# digitalBoardV1_1.net
KiCad netlist of a schematic drawn in EAGLE
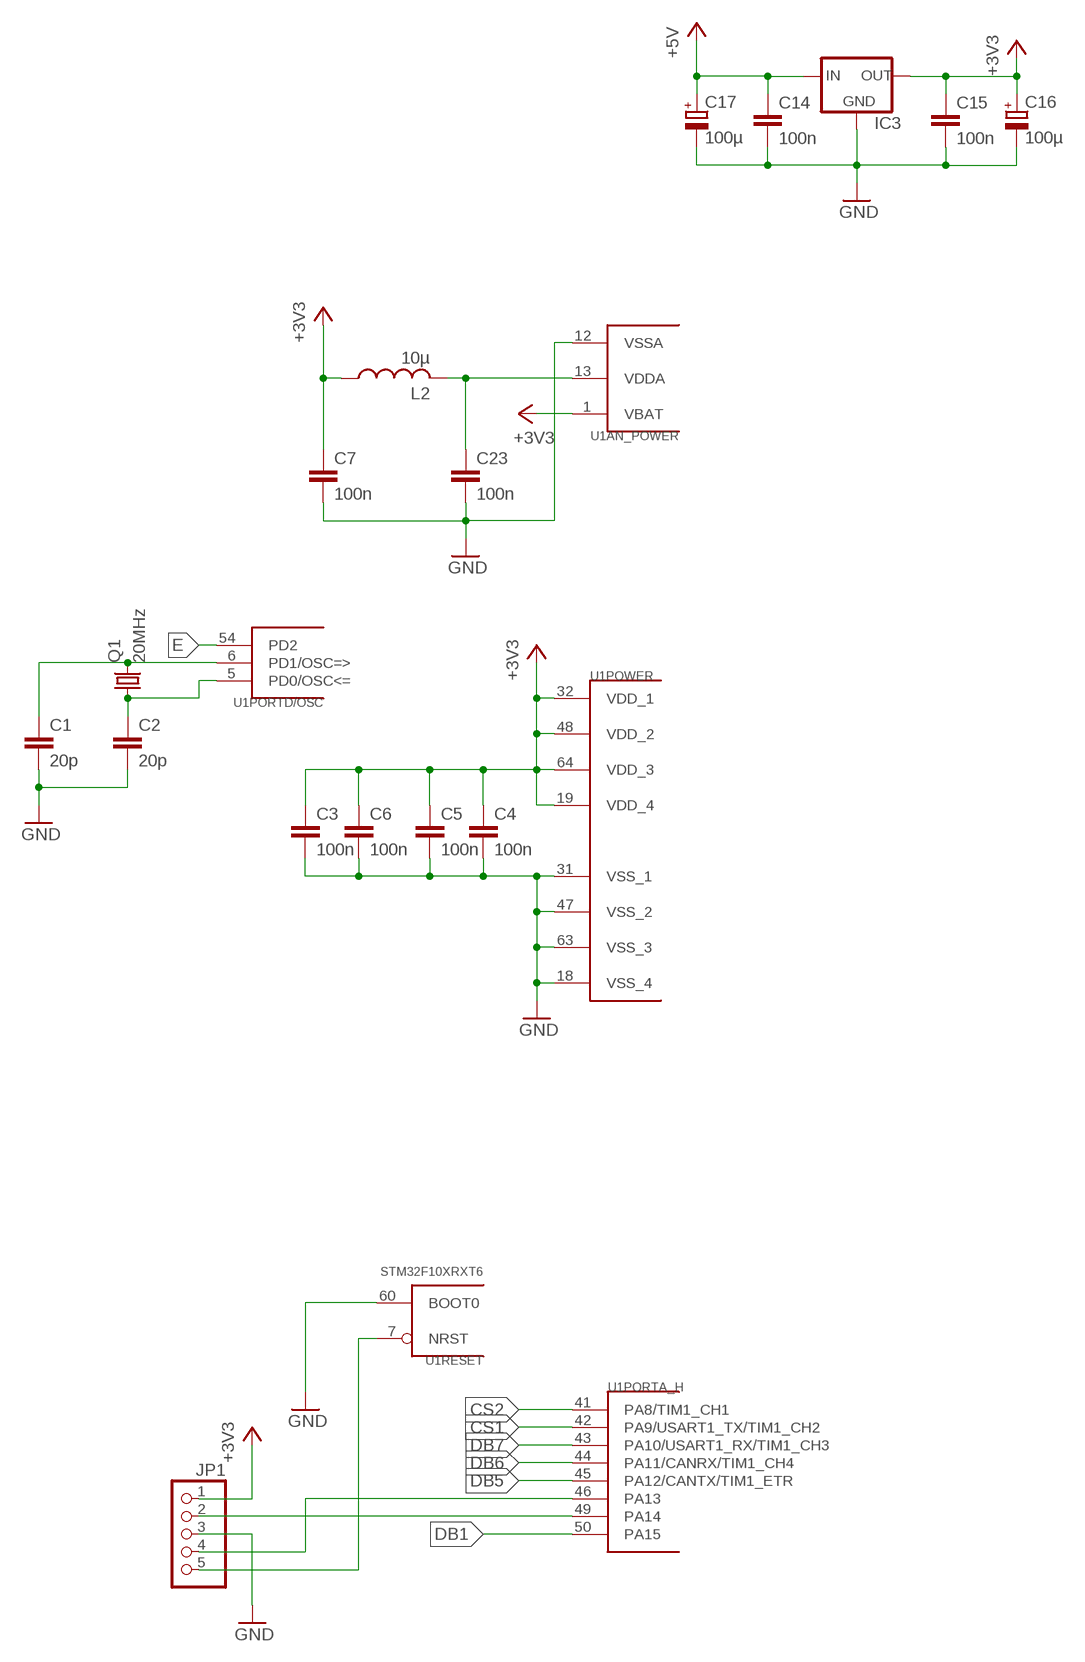
[diagram p0: schematic, sheet 1, part 1 of 2]
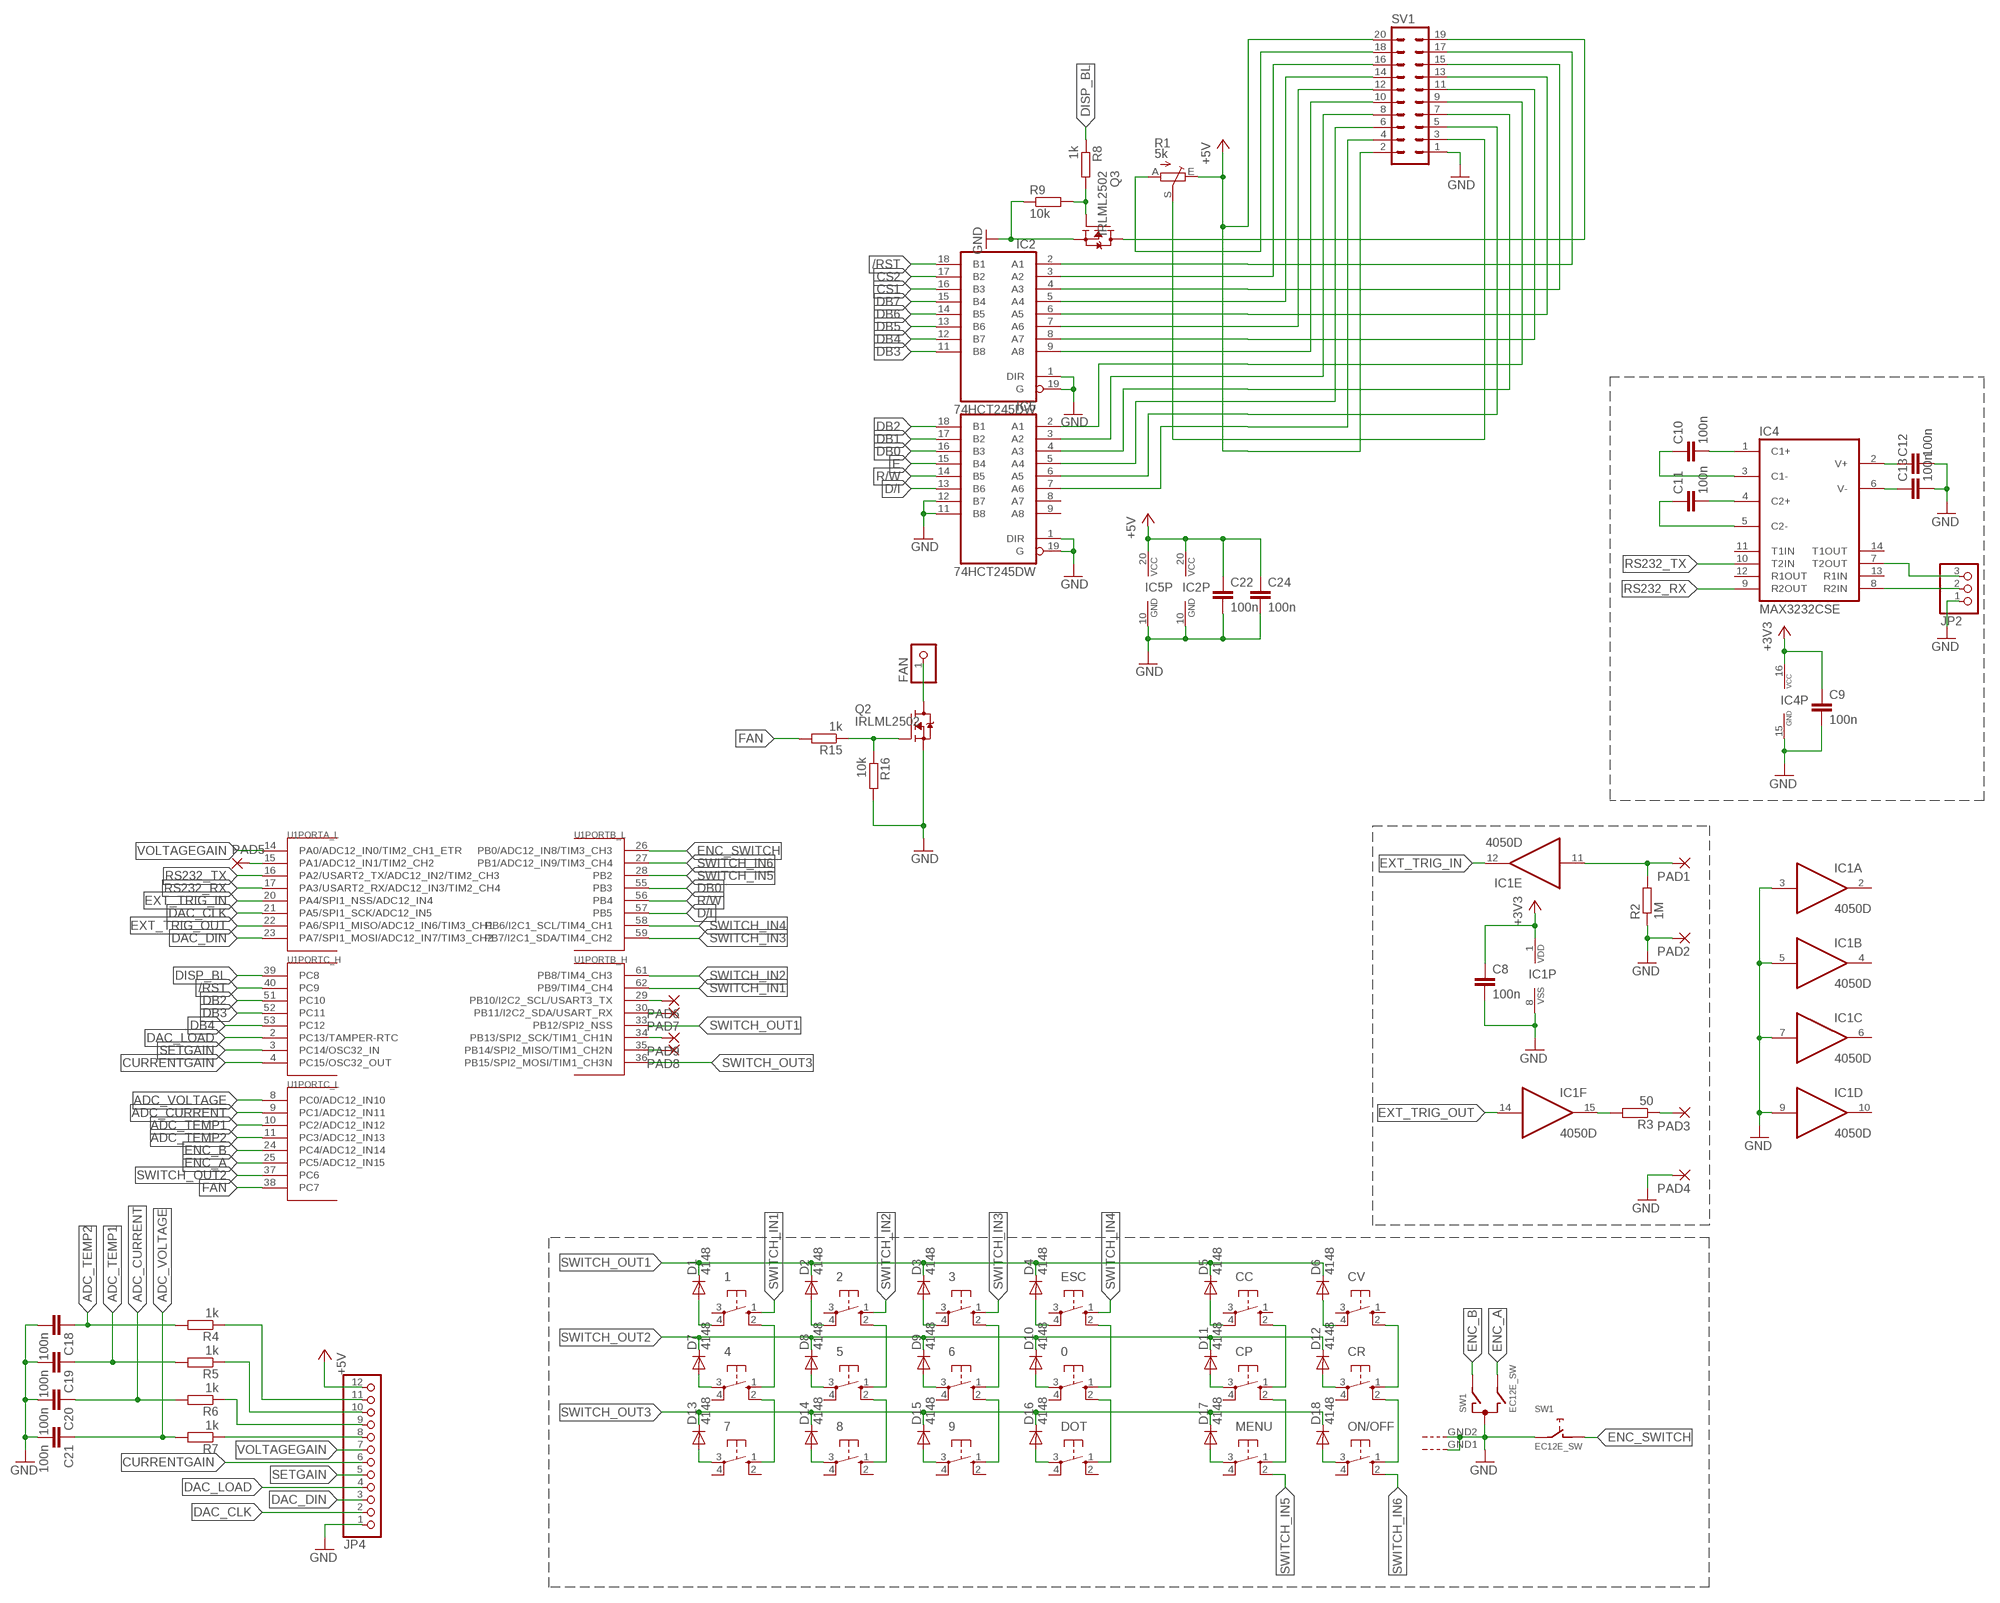
[diagram p1: schematic, sheet 1, part 2 of 2]

(export (version "E")
  (design (tool "Eeschema 10.0.6"))
  (components
    (comp (ref "0")
      (value "10-XXSMD")
      (footprint "eagle-import:SMD")
      (libsource (lib "eagle-import") (part "10-XXSMD"))
    )
    (comp (ref "1")
      (value "10-XXSMD")
      (footprint "eagle-import:SMD")
      (libsource (lib "eagle-import") (part "10-XXSMD"))
    )
    (comp (ref "2")
      (value "10-XXSMD")
      (footprint "eagle-import:SMD")
      (libsource (lib "eagle-import") (part "10-XXSMD"))
    )
    (comp (ref "3")
      (value "10-XXSMD")
      (footprint "eagle-import:SMD")
      (libsource (lib "eagle-import") (part "10-XXSMD"))
    )
    (comp (ref "4")
      (value "10-XXSMD")
      (footprint "eagle-import:SMD")
      (libsource (lib "eagle-import") (part "10-XXSMD"))
    )
    (comp (ref "5")
      (value "10-XXSMD")
      (footprint "eagle-import:SMD")
      (libsource (lib "eagle-import") (part "10-XXSMD"))
    )
    (comp (ref "6")
      (value "10-XXSMD")
      (footprint "eagle-import:SMD")
      (libsource (lib "eagle-import") (part "10-XXSMD"))
    )
    (comp (ref "7")
      (value "10-XXSMD")
      (footprint "eagle-import:SMD")
      (libsource (lib "eagle-import") (part "10-XXSMD"))
    )
    (comp (ref "8")
      (value "10-XXSMD")
      (footprint "eagle-import:SMD")
      (libsource (lib "eagle-import") (part "10-XXSMD"))
    )
    (comp (ref "9")
      (value "10-XXSMD")
      (footprint "eagle-import:SMD")
      (libsource (lib "eagle-import") (part "10-XXSMD"))
    )
    (comp (ref "C1")
      (value "20p")
      (footprint "eagle-import:C0603K")
      (libsource (lib "eagle-import") (part "C-EUC0603K"))
    )
    (comp (ref "C2")
      (value "20p")
      (footprint "eagle-import:C0603K")
      (libsource (lib "eagle-import") (part "C-EUC0603K"))
    )
    (comp (ref "C3")
      (value "100n")
      (footprint "eagle-import:C0603K")
      (libsource (lib "eagle-import") (part "C-EUC0603K"))
    )
    (comp (ref "C4")
      (value "100n")
      (footprint "eagle-import:C0603K")
      (libsource (lib "eagle-import") (part "C-EUC0603K"))
    )
    (comp (ref "C5")
      (value "100n")
      (footprint "eagle-import:C0603K")
      (libsource (lib "eagle-import") (part "C-EUC0603K"))
    )
    (comp (ref "C6")
      (value "100n")
      (footprint "eagle-import:C0603K")
      (libsource (lib "eagle-import") (part "C-EUC0603K"))
    )
    (comp (ref "C7")
      (value "100n")
      (footprint "eagle-import:C0603K")
      (libsource (lib "eagle-import") (part "C-EUC0603K"))
    )
    (comp (ref "C8")
      (value "100n")
      (footprint "eagle-import:C0603K")
      (libsource (lib "eagle-import") (part "C-EUC0603K"))
    )
    (comp (ref "C9")
      (value "100n")
      (footprint "eagle-import:C0603K")
      (libsource (lib "eagle-import") (part "C-EUC0603K"))
    )
    (comp (ref "C10")
      (value "100n")
      (footprint "eagle-import:C0603K")
      (libsource (lib "eagle-import") (part "C-EUC0603K"))
    )
    (comp (ref "C11")
      (value "100n")
      (footprint "eagle-import:C0603K")
      (libsource (lib "eagle-import") (part "C-EUC0603K"))
    )
    (comp (ref "C12")
      (value "100n")
      (footprint "eagle-import:C0603K")
      (libsource (lib "eagle-import") (part "C-EUC0603K"))
    )
    (comp (ref "C13")
      (value "100n")
      (footprint "eagle-import:C0603K")
      (libsource (lib "eagle-import") (part "C-EUC0603K"))
    )
    (comp (ref "C14")
      (value "100n")
      (footprint "eagle-import:C0603K")
      (libsource (lib "eagle-import") (part "C-EUC0603K"))
    )
    (comp (ref "C15")
      (value "100n")
      (footprint "eagle-import:C0603K")
      (libsource (lib "eagle-import") (part "C-EUC0603K"))
    )
    (comp (ref "C16")
      (value "100µ")
      (footprint "eagle-import:E2,5-6")
      (libsource (lib "eagle-import") (part "CPOL-EUE2.5-6"))
    )
    (comp (ref "C17")
      (value "100µ")
      (footprint "eagle-import:E2,5-6")
      (libsource (lib "eagle-import") (part "CPOL-EUE2.5-6"))
    )
    (comp (ref "C18")
      (value "100n")
      (footprint "eagle-import:C0603K")
      (libsource (lib "eagle-import") (part "C-EUC0603K"))
    )
    (comp (ref "C19")
      (value "100n")
      (footprint "eagle-import:C0603K")
      (libsource (lib "eagle-import") (part "C-EUC0603K"))
    )
    (comp (ref "C20")
      (value "100n")
      (footprint "eagle-import:C0603K")
      (libsource (lib "eagle-import") (part "C-EUC0603K"))
    )
    (comp (ref "C21")
      (value "100n")
      (footprint "eagle-import:C0603K")
      (libsource (lib "eagle-import") (part "C-EUC0603K"))
    )
    (comp (ref "C22")
      (value "100n")
      (footprint "eagle-import:C0603K")
      (libsource (lib "eagle-import") (part "C-EUC0603K"))
    )
    (comp (ref "C23")
      (value "100n")
      (footprint "eagle-import:C0603K")
      (libsource (lib "eagle-import") (part "C-EUC0603K"))
    )
    (comp (ref "C24")
      (value "100n")
      (footprint "eagle-import:C0603K")
      (libsource (lib "eagle-import") (part "C-EUC0603K"))
    )
    (comp (ref "CC")
      (value "10-XXSMD")
      (footprint "eagle-import:SMD")
      (libsource (lib "eagle-import") (part "10-XXSMD"))
    )
    (comp (ref "CP")
      (value "10-XXSMD")
      (footprint "eagle-import:SMD")
      (libsource (lib "eagle-import") (part "10-XXSMD"))
    )
    (comp (ref "CR")
      (value "10-XXSMD")
      (footprint "eagle-import:SMD")
      (libsource (lib "eagle-import") (part "10-XXSMD"))
    )
    (comp (ref "CV")
      (value "10-XXSMD")
      (footprint "eagle-import:SMD")
      (libsource (lib "eagle-import") (part "10-XXSMD"))
    )
    (comp (ref "D1")
      (value "4148")
      (footprint "eagle-import:SOD323-R")
      (libsource (lib "eagle-import") (part "DIODE-SOD323-R"))
    )
    (comp (ref "D2")
      (value "4148")
      (footprint "eagle-import:SOD323-R")
      (libsource (lib "eagle-import") (part "DIODE-SOD323-R"))
    )
    (comp (ref "D3")
      (value "4148")
      (footprint "eagle-import:SOD323-R")
      (libsource (lib "eagle-import") (part "DIODE-SOD323-R"))
    )
    (comp (ref "D4")
      (value "4148")
      (footprint "eagle-import:SOD323-R")
      (libsource (lib "eagle-import") (part "DIODE-SOD323-R"))
    )
    (comp (ref "D5")
      (value "4148")
      (footprint "eagle-import:SOD323-R")
      (libsource (lib "eagle-import") (part "DIODE-SOD323-R"))
    )
    (comp (ref "D6")
      (value "4148")
      (footprint "eagle-import:SOD323-R")
      (libsource (lib "eagle-import") (part "DIODE-SOD323-R"))
    )
    (comp (ref "D7")
      (value "4148")
      (footprint "eagle-import:SOD323-R")
      (libsource (lib "eagle-import") (part "DIODE-SOD323-R"))
    )
    (comp (ref "D8")
      (value "4148")
      (footprint "eagle-import:SOD323-R")
      (libsource (lib "eagle-import") (part "DIODE-SOD323-R"))
    )
    (comp (ref "D9")
      (value "4148")
      (footprint "eagle-import:SOD323-R")
      (libsource (lib "eagle-import") (part "DIODE-SOD323-R"))
    )
    (comp (ref "D10")
      (value "4148")
      (footprint "eagle-import:SOD323-R")
      (libsource (lib "eagle-import") (part "DIODE-SOD323-R"))
    )
    (comp (ref "D11")
      (value "4148")
      (footprint "eagle-import:SOD323-R")
      (libsource (lib "eagle-import") (part "DIODE-SOD323-R"))
    )
    (comp (ref "D12")
      (value "4148")
      (footprint "eagle-import:SOD323-R")
      (libsource (lib "eagle-import") (part "DIODE-SOD323-R"))
    )
    (comp (ref "D13")
      (value "4148")
      (footprint "eagle-import:SOD323-R")
      (libsource (lib "eagle-import") (part "DIODE-SOD323-R"))
    )
    (comp (ref "D14")
      (value "4148")
      (footprint "eagle-import:SOD323-R")
      (libsource (lib "eagle-import") (part "DIODE-SOD323-R"))
    )
    (comp (ref "D15")
      (value "4148")
      (footprint "eagle-import:SOD323-R")
      (libsource (lib "eagle-import") (part "DIODE-SOD323-R"))
    )
    (comp (ref "D16")
      (value "4148")
      (footprint "eagle-import:SOD323-R")
      (libsource (lib "eagle-import") (part "DIODE-SOD323-R"))
    )
    (comp (ref "D17")
      (value "4148")
      (footprint "eagle-import:SOD323-R")
      (libsource (lib "eagle-import") (part "DIODE-SOD323-R"))
    )
    (comp (ref "D18")
      (value "4148")
      (footprint "eagle-import:SOD323-R")
      (libsource (lib "eagle-import") (part "DIODE-SOD323-R"))
    )
    (comp (ref "DOT")
      (value "10-XXSMD")
      (footprint "eagle-import:SMD")
      (libsource (lib "eagle-import") (part "10-XXSMD"))
    )
    (comp (ref "ESC")
      (value "10-XXSMD")
      (footprint "eagle-import:SMD")
      (libsource (lib "eagle-import") (part "10-XXSMD"))
    )
    (comp (ref "FAN")
      (value "PINHD-1X1")
      (footprint "eagle-import:1X01")
      (libsource (lib "eagle-import") (part "PINHD-1X1"))
    )
    (comp (ref "IC1")
      (value "4050D")
      (footprint "eagle-import:SO16")
      (libsource (lib "eagle-import") (part "4050D"))
    )
    (comp (ref "IC2")
      (value "74HCT245DW")
      (footprint "eagle-import:SO20W")
      (libsource (lib "eagle-import") (part "74245DWHCT"))
    )
    (comp (ref "IC3")
      (value "LM1117")
      (footprint "eagle-import:SOT223")
      (libsource (lib "eagle-import") (part "LM1117"))
    )
    (comp (ref "IC4")
      (value "MAX3232CSE")
      (footprint "eagle-import:SO16")
      (libsource (lib "eagle-import") (part "MAX3232SEC"))
    )
    (comp (ref "IC5")
      (value "74HCT245DW")
      (footprint "eagle-import:SO20W")
      (libsource (lib "eagle-import") (part "74245DWHCT"))
    )
    (comp (ref "JP1")
      (value "PINHD-1X5")
      (footprint "eagle-import:1X05")
      (libsource (lib "eagle-import") (part "PINHD-1X5"))
    )
    (comp (ref "JP2")
      (value "PINHD-1X3")
      (footprint "eagle-import:1X03")
      (libsource (lib "eagle-import") (part "PINHD-1X3"))
    )
    (comp (ref "JP4")
      (value "PINHD-1X12")
      (footprint "eagle-import:1X12")
      (libsource (lib "eagle-import") (part "PINHD-1X12"))
    )
    (comp (ref "L2")
      (value "10µ")
      (footprint "eagle-import:R0805")
      (libsource (lib "eagle-import") (part "INDUCTOR0805"))
    )
    (comp (ref "MENU")
      (value "10-XXSMD")
      (footprint "eagle-import:SMD")
      (libsource (lib "eagle-import") (part "10-XXSMD"))
    )
    (comp (ref "ON/OFF")
      (value "10-XXSMD")
      (footprint "eagle-import:SMD")
      (libsource (lib "eagle-import") (part "10-XXSMD"))
    )
    (comp (ref "PAD1")
      (value "SMD2")
      (footprint "eagle-import:SMD1,27-2,54")
      (libsource (lib "eagle-import") (part "SMD2"))
    )
    (comp (ref "PAD2")
      (value "SMD2")
      (footprint "eagle-import:SMD1,27-2,54")
      (libsource (lib "eagle-import") (part "SMD2"))
    )
    (comp (ref "PAD3")
      (value "SMD2")
      (footprint "eagle-import:SMD1,27-2,54")
      (libsource (lib "eagle-import") (part "SMD2"))
    )
    (comp (ref "PAD4")
      (value "SMD2")
      (footprint "eagle-import:SMD1,27-2,54")
      (libsource (lib "eagle-import") (part "SMD2"))
    )
    (comp (ref "PAD5")
      (value "SMD2")
      (footprint "eagle-import:SMD1,27-2,54")
      (libsource (lib "eagle-import") (part "SMD2"))
    )
    (comp (ref "PAD6")
      (value "SMD2")
      (footprint "eagle-import:SMD1,27-2,54")
      (libsource (lib "eagle-import") (part "SMD2"))
    )
    (comp (ref "PAD7")
      (value "SMD2")
      (footprint "eagle-import:SMD1,27-2,54")
      (libsource (lib "eagle-import") (part "SMD2"))
    )
    (comp (ref "PAD8")
      (value "SMD2")
      (footprint "eagle-import:SMD1,27-2,54")
      (libsource (lib "eagle-import") (part "SMD2"))
    )
    (comp (ref "PAD9")
      (value "SMD2")
      (footprint "eagle-import:SMD1,27-2,54")
      (libsource (lib "eagle-import") (part "SMD2"))
    )
    (comp (ref "Q1")
      (value "20MHz")
      (footprint "eagle-import:CTS406")
      (libsource (lib "eagle-import") (part "CRYSTALCTS406"))
    )
    (comp (ref "Q2")
      (value "IRLML2502")
      (footprint "eagle-import:SOT23-3")
      (libsource (lib "eagle-import") (part "IRLML2502"))
    )
    (comp (ref "Q3")
      (value "IRLML2502")
      (footprint "eagle-import:SOT23-3")
      (libsource (lib "eagle-import") (part "IRLML2502"))
    )
    (comp (ref "R1")
      (value "5k")
      (footprint "eagle-import:RJ9W")
      (libsource (lib "eagle-import") (part "TRIM_EU-RJ9W"))
    )
    (comp (ref "R2")
      (value "1M")
      (footprint "eagle-import:R0603")
      (libsource (lib "eagle-import") (part "R-EU_R0603"))
    )
    (comp (ref "R3")
      (value "50")
      (footprint "eagle-import:R0603")
      (libsource (lib "eagle-import") (part "R-EU_R0603"))
    )
    (comp (ref "R4")
      (value "1k")
      (footprint "eagle-import:R0603")
      (libsource (lib "eagle-import") (part "R-EU_R0603"))
    )
    (comp (ref "R5")
      (value "1k")
      (footprint "eagle-import:R0603")
      (libsource (lib "eagle-import") (part "R-EU_R0603"))
    )
    (comp (ref "R6")
      (value "1k")
      (footprint "eagle-import:R0603")
      (libsource (lib "eagle-import") (part "R-EU_R0603"))
    )
    (comp (ref "R7")
      (value "1k")
      (footprint "eagle-import:R0603")
      (libsource (lib "eagle-import") (part "R-EU_R0603"))
    )
    (comp (ref "R8")
      (value "1k")
      (footprint "eagle-import:R0603")
      (libsource (lib "eagle-import") (part "R-EU_R0603"))
    )
    (comp (ref "R9")
      (value "10k")
      (footprint "eagle-import:R0603")
      (libsource (lib "eagle-import") (part "R-EU_R0603"))
    )
    (comp (ref "R15")
      (value "1k")
      (footprint "eagle-import:R0603")
      (libsource (lib "eagle-import") (part "R-EU_R0603"))
    )
    (comp (ref "R16")
      (value "10k")
      (footprint "eagle-import:R0603")
      (libsource (lib "eagle-import") (part "R-EU_R0603"))
    )
    (comp (ref "SV1")
      (value "ML20")
      (footprint "eagle-import:ML20")
      (libsource (lib "eagle-import") (part "ML20"))
    )
    (comp (ref "SW1")
      (value "EC12E_SW")
      (footprint "eagle-import:ALPS_EC12E_SW")
      (fields (field (name "MPN") "EC12E2424407"))
      (libsource (lib "eagle-import") (part "EC12E_SW"))
    )
    (comp (ref "U1")
      (value "STM32F10XRXT6")
      (footprint "eagle-import:TQFP64")
      (libsource (lib "eagle-import") (part "STM32F10XRXT6"))
    )
  )
  (nets
    (net (code "1") (name "+3V3") (class "Default")
      (node (ref "C15") (pin "1") (pinfunction "1_1") (pintype "passive"))
      (node (ref "C16") (pin "+") (pinfunction "+_+") (pintype "passive"))
      (node (ref "C3") (pin "1") (pinfunction "1_1") (pintype "passive"))
      (node (ref "C4") (pin "1") (pinfunction "1_1") (pintype "passive"))
      (node (ref "C5") (pin "1") (pinfunction "1_1") (pintype "passive"))
      (node (ref "C6") (pin "1") (pinfunction "1_1") (pintype "passive"))
      (node (ref "C7") (pin "1") (pinfunction "1_1") (pintype "passive"))
      (node (ref "C8") (pin "1") (pinfunction "1_1") (pintype "passive"))
      (node (ref "C9") (pin "1") (pinfunction "1_1") (pintype "passive"))
      (node (ref "IC1") (pin "1") (pinfunction "VDD_1") (pintype "power_in"))
      (node (ref "IC3") (pin "2") (pinfunction "OUT_2") (pintype "passive"))
      (node (ref "IC4") (pin "16") (pinfunction "VCC_16") (pintype "power_in"))
      (node (ref "JP1") (pin "1") (pinfunction "1_1") (pintype "passive"))
      (node (ref "L2") (pin "1") (pinfunction "1_1") (pintype "passive"))
      (node (ref "U1") (pin "1") (pinfunction "VBAT_1") (pintype "power_in"))
      (node (ref "U1") (pin "19") (pinfunction "VDD_4_19") (pintype "power_in"))
      (node (ref "U1") (pin "32") (pinfunction "VDD_1_32") (pintype "power_in"))
      (node (ref "U1") (pin "48") (pinfunction "VDD_2_48") (pintype "power_in"))
      (node (ref "U1") (pin "64") (pinfunction "VDD_3_64") (pintype "power_in"))
    )
    (net (code "2") (name "+5V") (class "Default")
      (node (ref "C14") (pin "1") (pinfunction "1_1") (pintype "passive"))
      (node (ref "C17") (pin "+") (pinfunction "+_+") (pintype "passive"))
      (node (ref "C22") (pin "1") (pinfunction "1_1") (pintype "passive"))
      (node (ref "C24") (pin "1") (pinfunction "1_1") (pintype "passive"))
      (node (ref "IC2") (pin "20") (pinfunction "VCC_20") (pintype "power_in"))
      (node (ref "IC3") (pin "3") (pinfunction "IN_3") (pintype "input"))
      (node (ref "IC5") (pin "20") (pinfunction "VCC_20") (pintype "power_in"))
      (node (ref "JP4") (pin "12") (pinfunction "12_12") (pintype "passive"))
      (node (ref "R1") (pin "E") (pinfunction "E_E") (pintype "passive"))
      (node (ref "SV1") (pin "2") (pinfunction "2_2") (pintype "passive"))
      (node (ref "SV1") (pin "20") (pinfunction "20_20") (pintype "passive"))
    )
    (net (code "3") (name "ADC_CURRENT") (class "Default")
      (node (ref "C20") (pin "1") (pinfunction "1_1") (pintype "passive"))
      (node (ref "R6") (pin "2") (pinfunction "2_2") (pintype "passive"))
      (node (ref "U1") (pin "9") (pinfunction "PC1/ADC12_IN11_9") (pintype "bidirectional"))
    )
    (net (code "4") (name "ADC_TEMP1") (class "Default")
      (node (ref "C19") (pin "1") (pinfunction "1_1") (pintype "passive"))
      (node (ref "R5") (pin "2") (pinfunction "2_2") (pintype "passive"))
      (node (ref "U1") (pin "10") (pinfunction "PC2/ADC12_IN12_10") (pintype "bidirectional"))
    )
    (net (code "5") (name "ADC_TEMP2") (class "Default")
      (node (ref "C18") (pin "1") (pinfunction "1_1") (pintype "passive"))
      (node (ref "R4") (pin "2") (pinfunction "2_2") (pintype "passive"))
      (node (ref "U1") (pin "11") (pinfunction "PC3/ADC12_IN13_11") (pintype "bidirectional"))
    )
    (net (code "6") (name "ADC_VOLTAGE") (class "Default")
      (node (ref "C21") (pin "1") (pinfunction "1_1") (pintype "passive"))
      (node (ref "R7") (pin "2") (pinfunction "2_2") (pintype "passive"))
      (node (ref "U1") (pin "8") (pinfunction "PC0/ADC12_IN10_8") (pintype "bidirectional"))
    )
    (net (code "7") (name "CS1") (class "Default")
      (node (ref "IC2") (pin "16") (pinfunction "B3_16") (pintype "bidirectional"))
      (node (ref "U1") (pin "42") (pinfunction "PA9/USART1_TX/TIM1_CH2_42") (pintype "bidirectional"))
    )
    (net (code "8") (name "CS2") (class "Default")
      (node (ref "IC2") (pin "17") (pinfunction "B2_17") (pintype "bidirectional"))
      (node (ref "U1") (pin "41") (pinfunction "PA8/TIM1_CH1_41") (pintype "bidirectional"))
    )
    (net (code "9") (name "CURRENTGAIN") (class "Default")
      (node (ref "JP4") (pin "6") (pinfunction "6_6") (pintype "passive"))
      (node (ref "U1") (pin "4") (pinfunction "PC15/OSC32_OUT_4") (pintype "bidirectional"))
    )
    (net (code "10") (name "DAC_CLK") (class "Default")
      (node (ref "JP4") (pin "2") (pinfunction "2_2") (pintype "passive"))
      (node (ref "U1") (pin "21") (pinfunction "PA5/SPI1_SCK/ADC12_IN5_21") (pintype "bidirectional"))
    )
    (net (code "11") (name "DAC_DIN") (class "Default")
      (node (ref "JP4") (pin "3") (pinfunction "3_3") (pintype "passive"))
      (node (ref "U1") (pin "23") (pinfunction "PA7/SPI1_MOSI/ADC12_IN7/TIM3_CH2_23") (pintype "bidirectional"))
    )
    (net (code "12") (name "DAC_LOAD") (class "Default")
      (node (ref "JP4") (pin "4") (pinfunction "4_4") (pintype "passive"))
      (node (ref "U1") (pin "2") (pinfunction "PC13/TAMPER-RTC_2") (pintype "bidirectional"))
    )
    (net (code "13") (name "DB0") (class "Default")
      (node (ref "IC5") (pin "16") (pinfunction "B3_16") (pintype "bidirectional"))
      (node (ref "U1") (pin "55") (pinfunction "PB3_55") (pintype "bidirectional"))
    )
    (net (code "14") (name "DB1") (class "Default")
      (node (ref "IC5") (pin "17") (pinfunction "B2_17") (pintype "bidirectional"))
      (node (ref "U1") (pin "50") (pinfunction "PA15_50") (pintype "bidirectional"))
    )
    (net (code "15") (name "DB2") (class "Default")
      (node (ref "IC5") (pin "18") (pinfunction "B1_18") (pintype "bidirectional"))
      (node (ref "U1") (pin "51") (pinfunction "PC10_51") (pintype "bidirectional"))
    )
    (net (code "16") (name "DB3") (class "Default")
      (node (ref "IC2") (pin "11") (pinfunction "B8_11") (pintype "bidirectional"))
      (node (ref "U1") (pin "52") (pinfunction "PC11_52") (pintype "bidirectional"))
    )
    (net (code "17") (name "DB4") (class "Default")
      (node (ref "IC2") (pin "12") (pinfunction "B7_12") (pintype "bidirectional"))
      (node (ref "U1") (pin "53") (pinfunction "PC12_53") (pintype "bidirectional"))
    )
    (net (code "18") (name "DB5") (class "Default")
      (node (ref "IC2") (pin "13") (pinfunction "B6_13") (pintype "bidirectional"))
      (node (ref "U1") (pin "45") (pinfunction "PA12/CANTX/TIM1_ETR_45") (pintype "bidirectional"))
    )
    (net (code "19") (name "DB6") (class "Default")
      (node (ref "IC2") (pin "14") (pinfunction "B5_14") (pintype "bidirectional"))
      (node (ref "U1") (pin "44") (pinfunction "PA11/CANRX/TIM1_CH4_44") (pintype "bidirectional"))
    )
    (net (code "20") (name "DB7") (class "Default")
      (node (ref "IC2") (pin "15") (pinfunction "B4_15") (pintype "bidirectional"))
      (node (ref "U1") (pin "43") (pinfunction "PA10/USART1_RX/TIM1_CH3_43") (pintype "bidirectional"))
    )
    (net (code "21") (name "DISP_BL") (class "Default")
      (node (ref "R8") (pin "1") (pinfunction "1_1") (pintype "passive"))
      (node (ref "U1") (pin "39") (pinfunction "PC8_39") (pintype "bidirectional"))
    )
    (net (code "22") (name "D{slash}I") (class "Default")
      (node (ref "IC5") (pin "13") (pinfunction "B6_13") (pintype "bidirectional"))
      (node (ref "U1") (pin "57") (pinfunction "PB5_57") (pintype "bidirectional"))
    )
    (net (code "23") (name "E") (class "Default")
      (node (ref "IC5") (pin "15") (pinfunction "B4_15") (pintype "bidirectional"))
      (node (ref "U1") (pin "54") (pinfunction "PD2_54") (pintype "bidirectional"))
    )
    (net (code "24") (name "ENC_A") (class "Default")
      (node (ref "SW1") (pin "B") (pinfunction "B_B") (pintype "passive"))
      (node (ref "U1") (pin "25") (pinfunction "PC5/ADC12_IN15_25") (pintype "bidirectional"))
    )
    (net (code "25") (name "ENC_B") (class "Default")
      (node (ref "SW1") (pin "A") (pinfunction "A_A") (pintype "passive"))
      (node (ref "U1") (pin "24") (pinfunction "PC4/ADC12_IN14_24") (pintype "bidirectional"))
    )
    (net (code "26") (name "ENC_SWITCH") (class "Default")
      (node (ref "SW1") (pin "D") (pinfunction "1_D") (pintype "passive"))
      (node (ref "U1") (pin "26") (pinfunction "PB0/ADC12_IN8/TIM3_CH3_26") (pintype "bidirectional"))
    )
    (net (code "27") (name "EXT_TRIG_IN") (class "Default")
      (node (ref "IC1") (pin "12") (pinfunction "O_12") (pintype "output"))
      (node (ref "U1") (pin "20") (pinfunction "PA4/SPI1_NSS/ADC12_IN4_20") (pintype "bidirectional"))
    )
    (net (code "28") (name "EXT_TRIG_OUT") (class "Default")
      (node (ref "IC1") (pin "14") (pinfunction "I_14") (pintype "input"))
      (node (ref "U1") (pin "22") (pinfunction "PA6/SPI1_MISO/ADC12_IN6/TIM3_CH1_22") (pintype "bidirectional"))
    )
    (net (code "29") (name "FAN") (class "Default")
      (node (ref "R15") (pin "2") (pinfunction "2_2") (pintype "passive"))
      (node (ref "U1") (pin "38") (pinfunction "PC7_38") (pintype "bidirectional"))
    )
    (net (code "30") (name "GND") (class "Default")
      (node (ref "C1") (pin "2") (pinfunction "2_2") (pintype "passive"))
      (node (ref "C12") (pin "2") (pinfunction "2_2") (pintype "passive"))
      (node (ref "C13") (pin "2") (pinfunction "2_2") (pintype "passive"))
      (node (ref "C14") (pin "2") (pinfunction "2_2") (pintype "passive"))
      (node (ref "C15") (pin "2") (pinfunction "2_2") (pintype "passive"))
      (node (ref "C16") (pin "-") (pinfunction "-_-") (pintype "passive"))
      (node (ref "C17") (pin "-") (pinfunction "-_-") (pintype "passive"))
      (node (ref "C18") (pin "2") (pinfunction "2_2") (pintype "passive"))
      (node (ref "C19") (pin "2") (pinfunction "2_2") (pintype "passive"))
      (node (ref "C2") (pin "2") (pinfunction "2_2") (pintype "passive"))
      (node (ref "C20") (pin "2") (pinfunction "2_2") (pintype "passive"))
      (node (ref "C21") (pin "2") (pinfunction "2_2") (pintype "passive"))
      (node (ref "C22") (pin "2") (pinfunction "2_2") (pintype "passive"))
      (node (ref "C23") (pin "2") (pinfunction "2_2") (pintype "passive"))
      (node (ref "C24") (pin "2") (pinfunction "2_2") (pintype "passive"))
      (node (ref "C3") (pin "2") (pinfunction "2_2") (pintype "passive"))
      (node (ref "C4") (pin "2") (pinfunction "2_2") (pintype "passive"))
      (node (ref "C5") (pin "2") (pinfunction "2_2") (pintype "passive"))
      (node (ref "C6") (pin "2") (pinfunction "2_2") (pintype "passive"))
      (node (ref "C7") (pin "2") (pinfunction "2_2") (pintype "passive"))
      (node (ref "C8") (pin "2") (pinfunction "2_2") (pintype "passive"))
      (node (ref "C9") (pin "2") (pinfunction "2_2") (pintype "passive"))
      (node (ref "IC1") (pin "3") (pinfunction "I_3") (pintype "input"))
      (node (ref "IC1") (pin "5") (pinfunction "I_5") (pintype "input"))
      (node (ref "IC1") (pin "7") (pinfunction "I_7") (pintype "input"))
      (node (ref "IC1") (pin "8") (pinfunction "VSS_8") (pintype "power_in"))
      (node (ref "IC1") (pin "9") (pinfunction "I_9") (pintype "input"))
      (node (ref "IC2") (pin "1") (pinfunction "DIR_1") (pintype "input"))
      (node (ref "IC2") (pin "10") (pinfunction "GND_10") (pintype "power_in"))
      (node (ref "IC2") (pin "19") (pinfunction "G_19") (pintype "input"))
      (node (ref "IC3") (pin "1") (pinfunction "GND_1") (pintype "input"))
      (node (ref "IC4") (pin "15") (pinfunction "GND_15") (pintype "power_in"))
      (node (ref "IC5") (pin "1") (pinfunction "DIR_1") (pintype "input"))
      (node (ref "IC5") (pin "10") (pinfunction "GND_10") (pintype "power_in"))
      (node (ref "IC5") (pin "11") (pinfunction "B8_11") (pintype "bidirectional"))
      (node (ref "IC5") (pin "12") (pinfunction "B7_12") (pintype "bidirectional"))
      (node (ref "IC5") (pin "19") (pinfunction "G_19") (pintype "input"))
      (node (ref "JP1") (pin "3") (pinfunction "3_3") (pintype "passive"))
      (node (ref "JP2") (pin "1") (pinfunction "1_1") (pintype "passive"))
      (node (ref "JP4") (pin "1") (pinfunction "1_1") (pintype "passive"))
      (node (ref "PAD2") (pin "1") (pinfunction "P_1") (pintype "passive"))
      (node (ref "PAD4") (pin "1") (pinfunction "P_1") (pintype "passive"))
      (node (ref "Q2") (pin "2") (pinfunction "S_2") (pintype "passive"))
      (node (ref "Q3") (pin "2") (pinfunction "S_2") (pintype "passive"))
      (node (ref "R16") (pin "2") (pinfunction "2_2") (pintype "passive"))
      (node (ref "R2") (pin "1") (pinfunction "1_1") (pintype "passive"))
      (node (ref "R9") (pin "1") (pinfunction "1_1") (pintype "passive"))
      (node (ref "SV1") (pin "1") (pinfunction "1_1") (pintype "passive"))
      (node (ref "SW1") (pin "C") (pinfunction "C_C") (pintype "passive"))
      (node (ref "SW1") (pin "E") (pinfunction "2_E") (pintype "passive"))
      (node (ref "SW1") (pin "GND1") (pinfunction "G_GND1") (pintype "passive"))
      (node (ref "SW1") (pin "GND2") (pinfunction "G_GND2") (pintype "passive"))
      (node (ref "U1") (pin "12") (pinfunction "VSSA_12") (pintype "power_in"))
      (node (ref "U1") (pin "18") (pinfunction "VSS_4_18") (pintype "power_in"))
      (node (ref "U1") (pin "31") (pinfunction "VSS_1_31") (pintype "power_in"))
      (node (ref "U1") (pin "47") (pinfunction "VSS_2_47") (pintype "power_in"))
      (node (ref "U1") (pin "60") (pinfunction "BOOT0_60") (pintype "input"))
      (node (ref "U1") (pin "63") (pinfunction "VSS_3_63") (pintype "power_in"))
    )
    (net (code "31") (name "Net-(0-P)") (class "Default")
      (node (ref "0") (pin "3") (pinfunction "P_3") (pintype "passive"))
      (node (ref "D10") (pin "A") (pinfunction "A_A") (pintype "passive"))
    )
    (net (code "32") (name "Net-(0-S)") (class "Default")
      (node (ref "0") (pin "1") (pinfunction "S_1") (pintype "passive"))
      (node (ref "ESC") (pin "2") (pinfunction "S1_2") (pintype "passive"))
    )
    (net (code "33") (name "Net-(0-S1)") (class "Default")
      (node (ref "0") (pin "2") (pinfunction "S1_2") (pintype "passive"))
      (node (ref "DOT") (pin "1") (pinfunction "S_1") (pintype "passive"))
    )
    (net (code "34") (name "Net-(1-P1)") (class "Default")
      (node (ref "1") (pin "4") (pinfunction "P1_4") (pintype "passive"))
      (node (ref "D1") (pin "A") (pinfunction "A_A") (pintype "passive"))
    )
    (net (code "35") (name "Net-(1-S1)") (class "Default")
      (node (ref "1") (pin "2") (pinfunction "S1_2") (pintype "passive"))
      (node (ref "4") (pin "1") (pinfunction "S_1") (pintype "passive"))
    )
    (net (code "36") (name "Net-(2-P1)") (class "Default")
      (node (ref "2") (pin "4") (pinfunction "P1_4") (pintype "passive"))
      (node (ref "D2") (pin "A") (pinfunction "A_A") (pintype "passive"))
    )
    (net (code "37") (name "Net-(2-S1)") (class "Default")
      (node (ref "2") (pin "2") (pinfunction "S1_2") (pintype "passive"))
      (node (ref "5") (pin "1") (pinfunction "S_1") (pintype "passive"))
    )
    (net (code "38") (name "Net-(3-P1)") (class "Default")
      (node (ref "3") (pin "4") (pinfunction "P1_4") (pintype "passive"))
      (node (ref "D3") (pin "A") (pinfunction "A_A") (pintype "passive"))
    )
    (net (code "39") (name "Net-(3-S1)") (class "Default")
      (node (ref "3") (pin "2") (pinfunction "S1_2") (pintype "passive"))
      (node (ref "6") (pin "1") (pinfunction "S_1") (pintype "passive"))
    )
    (net (code "40") (name "Net-(4-P)") (class "Default")
      (node (ref "4") (pin "3") (pinfunction "P_3") (pintype "passive"))
      (node (ref "D7") (pin "A") (pinfunction "A_A") (pintype "passive"))
    )
    (net (code "41") (name "Net-(4-S1)") (class "Default")
      (node (ref "4") (pin "2") (pinfunction "S1_2") (pintype "passive"))
      (node (ref "7") (pin "1") (pinfunction "S_1") (pintype "passive"))
    )
    (net (code "42") (name "Net-(5-P)") (class "Default")
      (node (ref "5") (pin "3") (pinfunction "P_3") (pintype "passive"))
      (node (ref "D8") (pin "A") (pinfunction "A_A") (pintype "passive"))
    )
    (net (code "43") (name "Net-(5-S1)") (class "Default")
      (node (ref "5") (pin "2") (pinfunction "S1_2") (pintype "passive"))
      (node (ref "8") (pin "1") (pinfunction "S_1") (pintype "passive"))
    )
    (net (code "44") (name "Net-(6-P)") (class "Default")
      (node (ref "6") (pin "3") (pinfunction "P_3") (pintype "passive"))
      (node (ref "D9") (pin "A") (pinfunction "A_A") (pintype "passive"))
    )
    (net (code "45") (name "Net-(6-S1)") (class "Default")
      (node (ref "6") (pin "2") (pinfunction "S1_2") (pintype "passive"))
      (node (ref "9") (pin "1") (pinfunction "S_1") (pintype "passive"))
    )
    (net (code "46") (name "Net-(7-P)") (class "Default")
      (node (ref "7") (pin "3") (pinfunction "P_3") (pintype "passive"))
      (node (ref "D13") (pin "A") (pinfunction "A_A") (pintype "passive"))
    )
    (net (code "47") (name "Net-(8-P)") (class "Default")
      (node (ref "8") (pin "3") (pinfunction "P_3") (pintype "passive"))
      (node (ref "D14") (pin "A") (pinfunction "A_A") (pintype "passive"))
    )
    (net (code "48") (name "Net-(9-P)") (class "Default")
      (node (ref "9") (pin "3") (pinfunction "P_3") (pintype "passive"))
      (node (ref "D15") (pin "A") (pinfunction "A_A") (pintype "passive"))
    )
    (net (code "49") (name "Net-(CC-P1)") (class "Default")
      (node (ref "CC") (pin "4") (pinfunction "P1_4") (pintype "passive"))
      (node (ref "D5") (pin "A") (pinfunction "A_A") (pintype "passive"))
    )
    (net (code "50") (name "Net-(CC-S1)") (class "Default")
      (node (ref "CC") (pin "2") (pinfunction "S1_2") (pintype "passive"))
      (node (ref "CP") (pin "1") (pinfunction "S_1") (pintype "passive"))
    )
    (net (code "51") (name "Net-(CP-P)") (class "Default")
      (node (ref "CP") (pin "3") (pinfunction "P_3") (pintype "passive"))
      (node (ref "D11") (pin "A") (pinfunction "A_A") (pintype "passive"))
    )
    (net (code "52") (name "Net-(CP-S1)") (class "Default")
      (node (ref "CP") (pin "2") (pinfunction "S1_2") (pintype "passive"))
      (node (ref "MENU") (pin "1") (pinfunction "S_1") (pintype "passive"))
    )
    (net (code "53") (name "Net-(CR-P)") (class "Default")
      (node (ref "CR") (pin "3") (pinfunction "P_3") (pintype "passive"))
      (node (ref "D12") (pin "A") (pinfunction "A_A") (pintype "passive"))
    )
    (net (code "54") (name "Net-(CR-S)") (class "Default")
      (node (ref "CR") (pin "1") (pinfunction "S_1") (pintype "passive"))
      (node (ref "CV") (pin "2") (pinfunction "S1_2") (pintype "passive"))
    )
    (net (code "55") (name "Net-(CR-S1)") (class "Default")
      (node (ref "CR") (pin "2") (pinfunction "S1_2") (pintype "passive"))
      (node (ref "ON/OFF") (pin "1") (pinfunction "S_1") (pintype "passive"))
    )
    (net (code "56") (name "Net-(CV-P1)") (class "Default")
      (node (ref "CV") (pin "4") (pinfunction "P1_4") (pintype "passive"))
      (node (ref "D6") (pin "A") (pinfunction "A_A") (pintype "passive"))
    )
    (net (code "57") (name "Net-(DOT-P)") (class "Default")
      (node (ref "D16") (pin "A") (pinfunction "A_A") (pintype "passive"))
      (node (ref "DOT") (pin "3") (pinfunction "P_3") (pintype "passive"))
    )
    (net (code "58") (name "Net-(ESC-P1)") (class "Default")
      (node (ref "D4") (pin "A") (pinfunction "A_A") (pintype "passive"))
      (node (ref "ESC") (pin "4") (pinfunction "P1_4") (pintype "passive"))
    )
    (net (code "59") (name "Net-(IC1E-I)") (class "Default")
      (node (ref "IC1") (pin "11") (pinfunction "I_11") (pintype "input"))
      (node (ref "PAD1") (pin "1") (pinfunction "P_1") (pintype "passive"))
      (node (ref "R2") (pin "2") (pinfunction "2_2") (pintype "passive"))
    )
    (net (code "60") (name "Net-(IC1F-O)") (class "Default")
      (node (ref "IC1") (pin "15") (pinfunction "O_15") (pintype "output"))
      (node (ref "R3") (pin "2") (pinfunction "2_2") (pintype "passive"))
    )
    (net (code "61") (name "Net-(IC2A-A1)") (class "Default")
      (node (ref "IC2") (pin "2") (pinfunction "A1_2") (pintype "bidirectional"))
      (node (ref "SV1") (pin "17") (pinfunction "17_17") (pintype "passive"))
    )
    (net (code "62") (name "Net-(IC2A-A2)") (class "Default")
      (node (ref "IC2") (pin "3") (pinfunction "A2_3") (pintype "bidirectional"))
      (node (ref "SV1") (pin "16") (pinfunction "16_16") (pintype "passive"))
    )
    (net (code "63") (name "Net-(IC2A-A3)") (class "Default")
      (node (ref "IC2") (pin "4") (pinfunction "A3_4") (pintype "bidirectional"))
      (node (ref "SV1") (pin "15") (pinfunction "15_15") (pintype "passive"))
    )
    (net (code "64") (name "Net-(IC2A-A4)") (class "Default")
      (node (ref "IC2") (pin "5") (pinfunction "A4_5") (pintype "bidirectional"))
      (node (ref "SV1") (pin "14") (pinfunction "14_14") (pintype "passive"))
    )
    (net (code "65") (name "Net-(IC2A-A5)") (class "Default")
      (node (ref "IC2") (pin "6") (pinfunction "A5_6") (pintype "bidirectional"))
      (node (ref "SV1") (pin "13") (pinfunction "13_13") (pintype "passive"))
    )
    (net (code "66") (name "Net-(IC2A-A6)") (class "Default")
      (node (ref "IC2") (pin "7") (pinfunction "A6_7") (pintype "bidirectional"))
      (node (ref "SV1") (pin "12") (pinfunction "12_12") (pintype "passive"))
    )
    (net (code "67") (name "Net-(IC2A-A7)") (class "Default")
      (node (ref "IC2") (pin "8") (pinfunction "A7_8") (pintype "bidirectional"))
      (node (ref "SV1") (pin "11") (pinfunction "11_11") (pintype "passive"))
    )
    (net (code "68") (name "Net-(IC2A-A8)") (class "Default")
      (node (ref "IC2") (pin "9") (pinfunction "A8_9") (pintype "bidirectional"))
      (node (ref "SV1") (pin "10") (pinfunction "10_10") (pintype "passive"))
    )
    (net (code "69") (name "Net-(IC4A-C1+)") (class "Default")
      (node (ref "C10") (pin "2") (pinfunction "2_2") (pintype "passive"))
      (node (ref "IC4") (pin "1") (pinfunction "C1+_1") (pintype "bidirectional"))
    )
    (net (code "70") (name "Net-(IC4A-C1-)") (class "Default")
      (node (ref "C10") (pin "1") (pinfunction "1_1") (pintype "passive"))
      (node (ref "IC4") (pin "3") (pinfunction "C1-_3") (pintype "bidirectional"))
    )
    (net (code "71") (name "Net-(IC4A-C2+)") (class "Default")
      (node (ref "C11") (pin "2") (pinfunction "2_2") (pintype "passive"))
      (node (ref "IC4") (pin "4") (pinfunction "C2+_4") (pintype "bidirectional"))
    )
    (net (code "72") (name "Net-(IC4A-C2-)") (class "Default")
      (node (ref "C11") (pin "1") (pinfunction "1_1") (pintype "passive"))
      (node (ref "IC4") (pin "5") (pinfunction "C2-_5") (pintype "bidirectional"))
    )
    (net (code "73") (name "Net-(IC4A-R2IN)") (class "Default")
      (node (ref "IC4") (pin "8") (pinfunction "R2IN_8") (pintype "input"))
      (node (ref "JP2") (pin "2") (pinfunction "2_2") (pintype "passive"))
    )
    (net (code "74") (name "Net-(IC4A-T2OUT)") (class "Default")
      (node (ref "IC4") (pin "7") (pinfunction "T2OUT_7") (pintype "output"))
      (node (ref "JP2") (pin "3") (pinfunction "3_3") (pintype "passive"))
    )
    (net (code "75") (name "Net-(IC4A-V+)") (class "Default")
      (node (ref "C12") (pin "1") (pinfunction "1_1") (pintype "passive"))
      (node (ref "IC4") (pin "2") (pinfunction "V+_2") (pintype "bidirectional"))
    )
    (net (code "76") (name "Net-(IC4A-V-)") (class "Default")
      (node (ref "C13") (pin "1") (pinfunction "1_1") (pintype "passive"))
      (node (ref "IC4") (pin "6") (pinfunction "V-_6") (pintype "bidirectional"))
    )
    (net (code "77") (name "Net-(IC5A-A1)") (class "Default")
      (node (ref "IC5") (pin "2") (pinfunction "A1_2") (pintype "bidirectional"))
      (node (ref "SV1") (pin "9") (pinfunction "9_9") (pintype "passive"))
    )
    (net (code "78") (name "Net-(IC5A-A2)") (class "Default")
      (node (ref "IC5") (pin "3") (pinfunction "A2_3") (pintype "bidirectional"))
      (node (ref "SV1") (pin "8") (pinfunction "8_8") (pintype "passive"))
    )
    (net (code "79") (name "Net-(IC5A-A3)") (class "Default")
      (node (ref "IC5") (pin "4") (pinfunction "A3_4") (pintype "bidirectional"))
      (node (ref "SV1") (pin "7") (pinfunction "7_7") (pintype "passive"))
    )
    (net (code "80") (name "Net-(IC5A-A4)") (class "Default")
      (node (ref "IC5") (pin "5") (pinfunction "A4_5") (pintype "bidirectional"))
      (node (ref "SV1") (pin "6") (pinfunction "6_6") (pintype "passive"))
    )
    (net (code "81") (name "Net-(IC5A-A5)") (class "Default")
      (node (ref "IC5") (pin "6") (pinfunction "A5_6") (pintype "bidirectional"))
      (node (ref "SV1") (pin "5") (pinfunction "5_5") (pintype "passive"))
    )
    (net (code "82") (name "Net-(IC5A-A6)") (class "Default")
      (node (ref "IC5") (pin "7") (pinfunction "A6_7") (pintype "bidirectional"))
      (node (ref "SV1") (pin "4") (pinfunction "4_4") (pintype "passive"))
    )
    (net (code "83") (name "Net-(JP4-Pad8)") (class "Default")
      (node (ref "JP4") (pin "8") (pinfunction "8_8") (pintype "passive"))
      (node (ref "R7") (pin "1") (pinfunction "1_1") (pintype "passive"))
    )
    (net (code "84") (name "Net-(JP4-Pad9)") (class "Default")
      (node (ref "JP4") (pin "9") (pinfunction "9_9") (pintype "passive"))
      (node (ref "R6") (pin "1") (pinfunction "1_1") (pintype "passive"))
    )
    (net (code "85") (name "Net-(JP4-Pad10)") (class "Default")
      (node (ref "JP4") (pin "10") (pinfunction "10_10") (pintype "passive"))
      (node (ref "R5") (pin "1") (pinfunction "1_1") (pintype "passive"))
    )
    (net (code "86") (name "Net-(JP4-Pad11)") (class "Default")
      (node (ref "JP4") (pin "11") (pinfunction "11_11") (pintype "passive"))
      (node (ref "R4") (pin "1") (pinfunction "1_1") (pintype "passive"))
    )
    (net (code "87") (name "Net-(MENU-P)") (class "Default")
      (node (ref "D17") (pin "A") (pinfunction "A_A") (pintype "passive"))
      (node (ref "MENU") (pin "3") (pinfunction "P_3") (pintype "passive"))
    )
    (net (code "88") (name "Net-(ON/OFF-P)") (class "Default")
      (node (ref "D18") (pin "A") (pinfunction "A_A") (pintype "passive"))
      (node (ref "ON/OFF") (pin "3") (pinfunction "P_3") (pintype "passive"))
    )
    (net (code "89") (name "Net-(PAD3-P)") (class "Default")
      (node (ref "PAD3") (pin "1") (pinfunction "P_1") (pintype "passive"))
      (node (ref "R3") (pin "1") (pinfunction "1_1") (pintype "passive"))
    )
    (net (code "90") (name "Net-(PAD5-P)") (class "Default")
      (node (ref "PAD5") (pin "1") (pinfunction "P_1") (pintype "passive"))
      (node (ref "U1") (pin "15") (pinfunction "PA1/ADC12_IN1/TIM2_CH2_15") (pintype "bidirectional"))
    )
    (net (code "91") (name "Net-(PAD6-P)") (class "Default")
      (node (ref "PAD6") (pin "1") (pinfunction "P_1") (pintype "passive"))
      (node (ref "U1") (pin "29") (pinfunction "PB10/I2C2_SCL/USART3_TX_29") (pintype "bidirectional"))
    )
    (net (code "92") (name "Net-(PAD7-P)") (class "Default")
      (node (ref "PAD7") (pin "1") (pinfunction "P_1") (pintype "passive"))
      (node (ref "U1") (pin "30") (pinfunction "PB11/I2C2_SDA/USART_RX_30") (pintype "bidirectional"))
    )
    (net (code "93") (name "Net-(PAD8-P)") (class "Default")
      (node (ref "PAD8") (pin "1") (pinfunction "P_1") (pintype "passive"))
      (node (ref "U1") (pin "35") (pinfunction "PB14/SPI2_MISO/TIM1_CH2N_35") (pintype "bidirectional"))
    )
    (net (code "94") (name "Net-(PAD9-P)") (class "Default")
      (node (ref "PAD9") (pin "1") (pinfunction "P_1") (pintype "passive"))
      (node (ref "U1") (pin "34") (pinfunction "PB13/SPI2_SCK/TIM1_CH1N_34") (pintype "bidirectional"))
    )
    (net (code "95") (name "Net-(Q1-2)") (class "Default")
      (node (ref "C1") (pin "1") (pinfunction "1_1") (pintype "passive"))
      (node (ref "Q1") (pin "3") (pinfunction "2_3") (pintype "passive"))
      (node (ref "U1") (pin "6") (pinfunction "PD1/OSC=>_6") (pintype "bidirectional"))
    )
    (net (code "96") (name "Net-(Q2-D)") (class "Default")
      (node (ref "FAN") (pin "1") (pinfunction "1_1") (pintype "passive"))
      (node (ref "Q2") (pin "3") (pinfunction "D_3") (pintype "passive"))
    )
    (net (code "97") (name "Net-(Q2-G)") (class "Default")
      (node (ref "Q2") (pin "1") (pinfunction "G_1") (pintype "passive"))
      (node (ref "R15") (pin "1") (pinfunction "1_1") (pintype "passive"))
      (node (ref "R16") (pin "1") (pinfunction "1_1") (pintype "passive"))
    )
    (net (code "98") (name "Net-(Q3-D)") (class "Default")
      (node (ref "Q3") (pin "3") (pinfunction "D_3") (pintype "passive"))
      (node (ref "SV1") (pin "19") (pinfunction "19_19") (pintype "passive"))
    )
    (net (code "99") (name "Net-(Q3-G)") (class "Default")
      (node (ref "Q3") (pin "1") (pinfunction "G_1") (pintype "passive"))
      (node (ref "R8") (pin "2") (pinfunction "2_2") (pintype "passive"))
      (node (ref "R9") (pin "2") (pinfunction "2_2") (pintype "passive"))
    )
    (net (code "100") (name "Net-(R1-PadA)") (class "Default")
      (node (ref "R1") (pin "A") (pinfunction "A_A") (pintype "passive"))
      (node (ref "SV1") (pin "18") (pinfunction "18_18") (pintype "passive"))
    )
    (net (code "101") (name "Net-(R1-PadS)") (class "Default")
      (node (ref "R1") (pin "S") (pinfunction "S_S") (pintype "passive"))
      (node (ref "SV1") (pin "3") (pinfunction "3_3") (pintype "passive"))
    )
    (net (code "102") (name "Net-(U1A-VDDA)") (class "Default")
      (node (ref "C23") (pin "1") (pinfunction "1_1") (pintype "passive"))
      (node (ref "L2") (pin "2") (pinfunction "2_2") (pintype "passive"))
      (node (ref "U1") (pin "13") (pinfunction "VDDA_13") (pintype "power_in"))
    )
    (net (code "103") (name "Net-(U1B-PA13)") (class "Default")
      (node (ref "JP1") (pin "4") (pinfunction "4_4") (pintype "passive"))
      (node (ref "U1") (pin "46") (pinfunction "PA13_46") (pintype "bidirectional"))
    )
    (net (code "104") (name "Net-(U1B-PA14)") (class "Default")
      (node (ref "JP1") (pin "2") (pinfunction "2_2") (pintype "passive"))
      (node (ref "U1") (pin "49") (pinfunction "PA14_49") (pintype "bidirectional"))
    )
    (net (code "105") (name "Net-(U1H-PD0{slash}OSC<=)") (class "Default")
      (node (ref "C2") (pin "1") (pinfunction "1_1") (pintype "passive"))
      (node (ref "Q1") (pin "1") (pinfunction "1_1") (pintype "passive"))
      (node (ref "U1") (pin "5") (pinfunction "PD0/OSC<=_5") (pintype "bidirectional"))
    )
    (net (code "106") (name "Net-(U1J-NRST)") (class "Default")
      (node (ref "JP1") (pin "5") (pinfunction "5_5") (pintype "passive"))
      (node (ref "U1") (pin "7") (pinfunction "NRST_7") (pintype "input"))
    )
    (net (code "107") (name "RS232_RX") (class "Default")
      (node (ref "IC4") (pin "9") (pinfunction "R2OUT_9") (pintype "output"))
      (node (ref "U1") (pin "17") (pinfunction "PA3/USART2_RX/ADC12_IN3/TIM2_CH4_17") (pintype "bidirectional"))
    )
    (net (code "108") (name "RS232_TX") (class "Default")
      (node (ref "IC4") (pin "10") (pinfunction "T2IN_10") (pintype "input"))
      (node (ref "U1") (pin "16") (pinfunction "PA2/USART2_TX/ADC12_IN2/TIM2_CH3_16") (pintype "bidirectional"))
    )
    (net (code "109") (name "R{slash}W") (class "Default")
      (node (ref "IC5") (pin "14") (pinfunction "B5_14") (pintype "bidirectional"))
      (node (ref "U1") (pin "56") (pinfunction "PB4_56") (pintype "bidirectional"))
    )
    (net (code "110") (name "SETGAIN") (class "Default")
      (node (ref "JP4") (pin "5") (pinfunction "5_5") (pintype "passive"))
      (node (ref "U1") (pin "3") (pinfunction "PC14/OSC32_IN_3") (pintype "bidirectional"))
    )
    (net (code "111") (name "SWITCH_IN1") (class "Default")
      (node (ref "1") (pin "1") (pinfunction "S_1") (pintype "passive"))
      (node (ref "U1") (pin "62") (pinfunction "PB9/TIM4_CH4_62") (pintype "bidirectional"))
    )
    (net (code "112") (name "SWITCH_IN2") (class "Default")
      (node (ref "2") (pin "1") (pinfunction "S_1") (pintype "passive"))
      (node (ref "U1") (pin "61") (pinfunction "PB8/TIM4_CH3_61") (pintype "bidirectional"))
    )
    (net (code "113") (name "SWITCH_IN3") (class "Default")
      (node (ref "3") (pin "1") (pinfunction "S_1") (pintype "passive"))
      (node (ref "U1") (pin "59") (pinfunction "PB7/I2C1_SDA/TIM4_CH2_59") (pintype "bidirectional"))
    )
    (net (code "114") (name "SWITCH_IN4") (class "Default")
      (node (ref "ESC") (pin "1") (pinfunction "S_1") (pintype "passive"))
      (node (ref "U1") (pin "58") (pinfunction "PB6/I2C1_SCL/TIM4_CH1_58") (pintype "bidirectional"))
    )
    (net (code "115") (name "SWITCH_IN5") (class "Default")
      (node (ref "MENU") (pin "2") (pinfunction "S1_2") (pintype "passive"))
      (node (ref "U1") (pin "28") (pinfunction "PB2_28") (pintype "bidirectional"))
    )
    (net (code "116") (name "SWITCH_IN6") (class "Default")
      (node (ref "ON/OFF") (pin "2") (pinfunction "S1_2") (pintype "passive"))
      (node (ref "U1") (pin "27") (pinfunction "PB1/ADC12_IN9/TIM3_CH4_27") (pintype "bidirectional"))
    )
    (net (code "117") (name "SWITCH_OUT1") (class "Default")
      (node (ref "D1") (pin "C") (pinfunction "C_C") (pintype "passive"))
      (node (ref "D2") (pin "C") (pinfunction "C_C") (pintype "passive"))
      (node (ref "D3") (pin "C") (pinfunction "C_C") (pintype "passive"))
      (node (ref "D4") (pin "C") (pinfunction "C_C") (pintype "passive"))
      (node (ref "D5") (pin "C") (pinfunction "C_C") (pintype "passive"))
      (node (ref "D6") (pin "C") (pinfunction "C_C") (pintype "passive"))
      (node (ref "U1") (pin "33") (pinfunction "PB12/SPI2_NSS_33") (pintype "bidirectional"))
    )
    (net (code "118") (name "SWITCH_OUT2") (class "Default")
      (node (ref "D10") (pin "C") (pinfunction "C_C") (pintype "passive"))
      (node (ref "D11") (pin "C") (pinfunction "C_C") (pintype "passive"))
      (node (ref "D12") (pin "C") (pinfunction "C_C") (pintype "passive"))
      (node (ref "D7") (pin "C") (pinfunction "C_C") (pintype "passive"))
      (node (ref "D8") (pin "C") (pinfunction "C_C") (pintype "passive"))
      (node (ref "D9") (pin "C") (pinfunction "C_C") (pintype "passive"))
      (node (ref "U1") (pin "37") (pinfunction "PC6_37") (pintype "bidirectional"))
    )
    (net (code "119") (name "SWITCH_OUT3") (class "Default")
      (node (ref "D13") (pin "C") (pinfunction "C_C") (pintype "passive"))
      (node (ref "D14") (pin "C") (pinfunction "C_C") (pintype "passive"))
      (node (ref "D15") (pin "C") (pinfunction "C_C") (pintype "passive"))
      (node (ref "D16") (pin "C") (pinfunction "C_C") (pintype "passive"))
      (node (ref "D17") (pin "C") (pinfunction "C_C") (pintype "passive"))
      (node (ref "D18") (pin "C") (pinfunction "C_C") (pintype "passive"))
      (node (ref "U1") (pin "36") (pinfunction "PB15/SPI2_MOSI/TIM1_CH3N_36") (pintype "bidirectional"))
    )
    (net (code "120") (name "VOLTAGEGAIN") (class "Default")
      (node (ref "JP4") (pin "7") (pinfunction "7_7") (pintype "passive"))
      (node (ref "U1") (pin "14") (pinfunction "PA0/ADC12_IN0/TIM2_CH1_ETR_14") (pintype "bidirectional"))
    )
    (net (code "121") (name "unconnected-(0-P1-Pad4)") (class "Default")
      (node (ref "0") (pin "4") (pinfunction "P1_4") (pintype "passive"))
    )
    (net (code "122") (name "unconnected-(1-P-Pad3)") (class "Default")
      (node (ref "1") (pin "3") (pinfunction "P_3") (pintype "passive"))
    )
    (net (code "123") (name "unconnected-(2-P-Pad3)") (class "Default")
      (node (ref "2") (pin "3") (pinfunction "P_3") (pintype "passive"))
    )
    (net (code "124") (name "unconnected-(3-P-Pad3)") (class "Default")
      (node (ref "3") (pin "3") (pinfunction "P_3") (pintype "passive"))
    )
    (net (code "125") (name "unconnected-(4-P1-Pad4)") (class "Default")
      (node (ref "4") (pin "4") (pinfunction "P1_4") (pintype "passive"))
    )
    (net (code "126") (name "unconnected-(5-P1-Pad4)") (class "Default")
      (node (ref "5") (pin "4") (pinfunction "P1_4") (pintype "passive"))
    )
    (net (code "127") (name "unconnected-(6-P1-Pad4)") (class "Default")
      (node (ref "6") (pin "4") (pinfunction "P1_4") (pintype "passive"))
    )
    (net (code "128") (name "unconnected-(7-P1-Pad4)") (class "Default")
      (node (ref "7") (pin "4") (pinfunction "P1_4") (pintype "passive"))
    )
    (net (code "129") (name "unconnected-(7-S1-Pad2)") (class "Default")
      (node (ref "7") (pin "2") (pinfunction "S1_2") (pintype "passive"))
    )
    (net (code "130") (name "unconnected-(8-P1-Pad4)") (class "Default")
      (node (ref "8") (pin "4") (pinfunction "P1_4") (pintype "passive"))
    )
    (net (code "131") (name "unconnected-(8-S1-Pad2)") (class "Default")
      (node (ref "8") (pin "2") (pinfunction "S1_2") (pintype "passive"))
    )
    (net (code "132") (name "unconnected-(9-P1-Pad4)") (class "Default")
      (node (ref "9") (pin "4") (pinfunction "P1_4") (pintype "passive"))
    )
    (net (code "133") (name "unconnected-(9-S1-Pad2)") (class "Default")
      (node (ref "9") (pin "2") (pinfunction "S1_2") (pintype "passive"))
    )
    (net (code "134") (name "unconnected-(CC-P-Pad3)") (class "Default")
      (node (ref "CC") (pin "3") (pinfunction "P_3") (pintype "passive"))
    )
    (net (code "135") (name "unconnected-(CC-S-Pad1)") (class "Default")
      (node (ref "CC") (pin "1") (pinfunction "S_1") (pintype "passive"))
    )
    (net (code "136") (name "unconnected-(CP-P1-Pad4)") (class "Default")
      (node (ref "CP") (pin "4") (pinfunction "P1_4") (pintype "passive"))
    )
    (net (code "137") (name "unconnected-(CR-P1-Pad4)") (class "Default")
      (node (ref "CR") (pin "4") (pinfunction "P1_4") (pintype "passive"))
    )
    (net (code "138") (name "unconnected-(CV-P-Pad3)") (class "Default")
      (node (ref "CV") (pin "3") (pinfunction "P_3") (pintype "passive"))
    )
    (net (code "139") (name "unconnected-(CV-S-Pad1)") (class "Default")
      (node (ref "CV") (pin "1") (pinfunction "S_1") (pintype "passive"))
    )
    (net (code "140") (name "unconnected-(DOT-P1-Pad4)") (class "Default")
      (node (ref "DOT") (pin "4") (pinfunction "P1_4") (pintype "passive"))
    )
    (net (code "141") (name "unconnected-(DOT-S1-Pad2)") (class "Default")
      (node (ref "DOT") (pin "2") (pinfunction "S1_2") (pintype "passive"))
    )
    (net (code "142") (name "unconnected-(ESC-P-Pad3)") (class "Default")
      (node (ref "ESC") (pin "3") (pinfunction "P_3") (pintype "passive"))
    )
    (net (code "143") (name "unconnected-(IC1A-O-Pad2)") (class "Default")
      (node (ref "IC1") (pin "2") (pinfunction "O_2") (pintype "output"))
    )
    (net (code "144") (name "unconnected-(IC1B-O-Pad4)") (class "Default")
      (node (ref "IC1") (pin "4") (pinfunction "O_4") (pintype "output"))
    )
    (net (code "145") (name "unconnected-(IC1C-O-Pad6)") (class "Default")
      (node (ref "IC1") (pin "6") (pinfunction "O_6") (pintype "output"))
    )
    (net (code "146") (name "unconnected-(IC1D-O-Pad10)") (class "Default")
      (node (ref "IC1") (pin "10") (pinfunction "O_10") (pintype "output"))
    )
    (net (code "147") (name "unconnected-(IC4A-R1IN-Pad13)") (class "Default")
      (node (ref "IC4") (pin "13") (pinfunction "R1IN_13") (pintype "input"))
    )
    (net (code "148") (name "unconnected-(IC4A-R1OUT-Pad12)") (class "Default")
      (node (ref "IC4") (pin "12") (pinfunction "R1OUT_12") (pintype "output"))
    )
    (net (code "149") (name "unconnected-(IC4A-T1IN-Pad11)") (class "Default")
      (node (ref "IC4") (pin "11") (pinfunction "T1IN_11") (pintype "input"))
    )
    (net (code "150") (name "unconnected-(IC4A-T1OUT-Pad14)") (class "Default")
      (node (ref "IC4") (pin "14") (pinfunction "T1OUT_14") (pintype "output"))
    )
    (net (code "151") (name "unconnected-(IC5A-A7-Pad8)") (class "Default")
      (node (ref "IC5") (pin "8") (pinfunction "A7_8") (pintype "bidirectional"))
    )
    (net (code "152") (name "unconnected-(IC5A-A8-Pad9)") (class "Default")
      (node (ref "IC5") (pin "9") (pinfunction "A8_9") (pintype "bidirectional"))
    )
    (net (code "153") (name "unconnected-(MENU-P1-Pad4)") (class "Default")
      (node (ref "MENU") (pin "4") (pinfunction "P1_4") (pintype "passive"))
    )
    (net (code "154") (name "unconnected-(ON/OFF-P1-Pad4)") (class "Default")
      (node (ref "ON/OFF") (pin "4") (pinfunction "P1_4") (pintype "passive"))
    )
    (net (code "155") (name "{slash}RST") (class "Default")
      (node (ref "IC2") (pin "18") (pinfunction "B1_18") (pintype "bidirectional"))
      (node (ref "U1") (pin "40") (pinfunction "PC9_40") (pintype "bidirectional"))
    )
  )
)
